# IO_Expander.net
KiCad netlist of a schematic drawn in Altium Designer
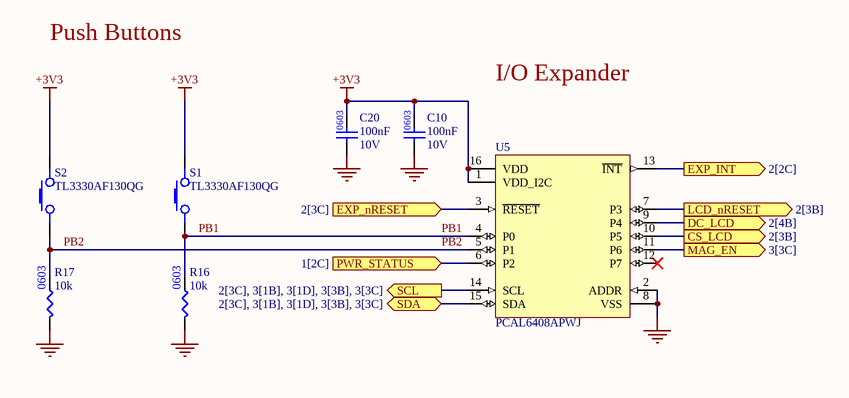
[diagram p0: IO_Expander.SchDoc]

(export (version "E")
  (design (tool "Eeschema 10.0.6"))
  (components
    (comp (ref "C10")
      (value "CC0603KRX7R6BB104")
      (footprint "CAP_0603")
      (description "CAP CER 0.1UF 10V X7R 0603")
      (fields
        (field (name "MANUFACTURER") "Yageo")
        (field (name "TOLERANCE") "10%")
        (field (name "CAPACITANCE") "100nF")
        (field (name "VOLTAGE RATING") "10V")
      )
      (libsource (lib "Smartwatch_Lib") (part "CC0603KRX7R6BB104"))
    )
    (comp (ref "C20")
      (value "CC0603KRX7R6BB104")
      (footprint "CAP_0603")
      (description "CAP CER 0.1UF 10V X7R 0603")
      (fields
        (field (name "MANUFACTURER") "Yageo")
        (field (name "TOLERANCE") "10%")
        (field (name "CAPACITANCE") "100nF")
        (field (name "VOLTAGE RATING") "10V")
      )
      (libsource (lib "Smartwatch_Lib") (part "CC0603KRX7R6BB104"))
    )
    (comp (ref "R16")
      (value "RNCP0603FTD10K0")
      (footprint "RES_0603")
      (description "Res Thin Film 0603 10K Ohm 1% 1/8W ±100ppm/°C Molded SMD SMD Paper T/R")
      (fields
        (field (name "MANUFACTURER") "Stackpole Electronics")
        (field (name "TOLERANCE") "1%")
        (field (name "RESISTANCE") "10k")
      )
      (libsource (lib "Smartwatch_Lib") (part "RNCP0603FTD10K0"))
    )
    (comp (ref "R17")
      (value "RNCP0603FTD10K0")
      (footprint "RES_0603")
      (description "Res Thin Film 0603 10K Ohm 1% 1/8W ±100ppm/°C Molded SMD SMD Paper T/R")
      (fields
        (field (name "MANUFACTURER") "Stackpole Electronics")
        (field (name "TOLERANCE") "1%")
        (field (name "RESISTANCE") "10k")
      )
      (libsource (lib "Smartwatch_Lib") (part "RNCP0603FTD10K0"))
    )
    (comp (ref "S1")
      (value "TL3330AF130QG")
      (footprint "TL3330AF130QG")
      (description "Switch Tactile N.O. SPST Rectangular Button Gull Wing 0.05A 12VDC 50000Cycles 1.27N SMD T/R")
      (fields
        (field (name "MANUFACTURER") "E-Switch")
        (field (name "MANUFACTURER PART NUMBER") "TL3330AF130QG")
      )
      (libsource (lib "Smartwatch_Lib") (part "TL3330AF130QG"))
    )
    (comp (ref "S2")
      (value "TL3330AF130QG")
      (footprint "TL3330AF130QG")
      (description "Switch Tactile N.O. SPST Rectangular Button Gull Wing 0.05A 12VDC 50000Cycles 1.27N SMD T/R")
      (fields
        (field (name "MANUFACTURER") "E-Switch")
        (field (name "MANUFACTURER PART NUMBER") "TL3330AF130QG")
      )
      (libsource (lib "Smartwatch_Lib") (part "TL3330AF130QG"))
    )
    (comp (ref "U5")
      (value "PCAL6408APWJ")
      (footprint "PCAL6408APWJ")
      (description "NXP - PCAL6408APWJ - I/O-Erweiterung, 8bit, 400 kHz, I2C, 1.65 V, 5.5 V, TSSOP")
      (fields
        (field (name "MANUFACTURER") "NXP Semiconductors")
        (field (name "MANUFACTURER PART NUMBER") "PCAL6408APWJ")
      )
      (libsource (lib "Smartwatch_Lib") (part "PCAL6408APWJ"))
    )
  )
  (nets
    (net (code "1") (name "+3V3") (class "Default")
      (node (ref "C10") (pin "2") (pinfunction "2_2") (pintype "passive"))
      (node (ref "C20") (pin "2") (pinfunction "2_2") (pintype "passive"))
      (node (ref "S1") (pin "1") (pintype "passive"))
      (node (ref "S2") (pin "1") (pintype "passive"))
      (node (ref "U5") (pin "1") (pinfunction "VDD_I2C_1") (pintype "power_in"))
      (node (ref "U5") (pin "16") (pinfunction "VDD_16") (pintype "power_in"))
    )
    (net (code "2") (name "/CS_LCD") (class "Default")
      (node (ref "U5") (pin "10") (pinfunction "P5_10") (pintype "bidirectional"))
    )
    (net (code "3") (name "/DC_LCD") (class "Default")
      (node (ref "U5") (pin "9") (pinfunction "P4_9") (pintype "bidirectional"))
    )
    (net (code "4") (name "/EXP_INT") (class "Default")
      (node (ref "U5") (pin "13") (pinfunction "~{INT}_13") (pintype "output"))
    )
    (net (code "5") (name "/EXP_nRESET") (class "Default")
      (node (ref "U5") (pin "3") (pinfunction "~{RESET}_3") (pintype "input"))
    )
    (net (code "6") (name "/LCD_nRESET") (class "Default")
      (node (ref "U5") (pin "7") (pinfunction "P3_7") (pintype "bidirectional"))
    )
    (net (code "7") (name "/MAG_EN") (class "Default")
      (node (ref "U5") (pin "11") (pinfunction "P6_11") (pintype "bidirectional"))
    )
    (net (code "8") (name "/PB1") (class "Default")
      (node (ref "R16") (pin "2") (pinfunction "2_2") (pintype "passive"))
      (node (ref "S1") (pin "2") (pintype "passive"))
      (node (ref "U5") (pin "4") (pinfunction "P0_4") (pintype "bidirectional"))
    )
    (net (code "9") (name "/PB2") (class "Default")
      (node (ref "R17") (pin "2") (pinfunction "2_2") (pintype "passive"))
      (node (ref "S2") (pin "2") (pintype "passive"))
      (node (ref "U5") (pin "5") (pinfunction "P1_5") (pintype "bidirectional"))
    )
    (net (code "10") (name "/PWR_STATUS") (class "Default")
      (node (ref "U5") (pin "6") (pinfunction "P2_6") (pintype "bidirectional"))
    )
    (net (code "11") (name "/SCL") (class "Default")
      (node (ref "U5") (pin "14") (pinfunction "SCL_14") (pintype "input"))
    )
    (net (code "12") (name "/SDA") (class "Default")
      (node (ref "U5") (pin "15") (pinfunction "SDA_15") (pintype "bidirectional"))
    )
    (net (code "13") (name "GND") (class "Default")
      (node (ref "C10") (pin "1") (pinfunction "1_1") (pintype "passive"))
      (node (ref "C20") (pin "1") (pinfunction "1_1") (pintype "passive"))
      (node (ref "R16") (pin "1") (pinfunction "1_1") (pintype "passive"))
      (node (ref "R17") (pin "1") (pinfunction "1_1") (pintype "passive"))
      (node (ref "U5") (pin "2") (pinfunction "ADDR_2") (pintype "input"))
      (node (ref "U5") (pin "8") (pinfunction "VSS_8") (pintype "power_in"))
    )
    (net (code "14") (name "unconnected-(U5-P7-Pad12)") (class "Default")
      (node (ref "U5") (pin "12") (pinfunction "P7_12") (pintype "bidirectional+no_connect"))
    )
  )
)
